# bottom_simp_gyro.net
KiCad netlist of a schematic drawn in Altium Designer
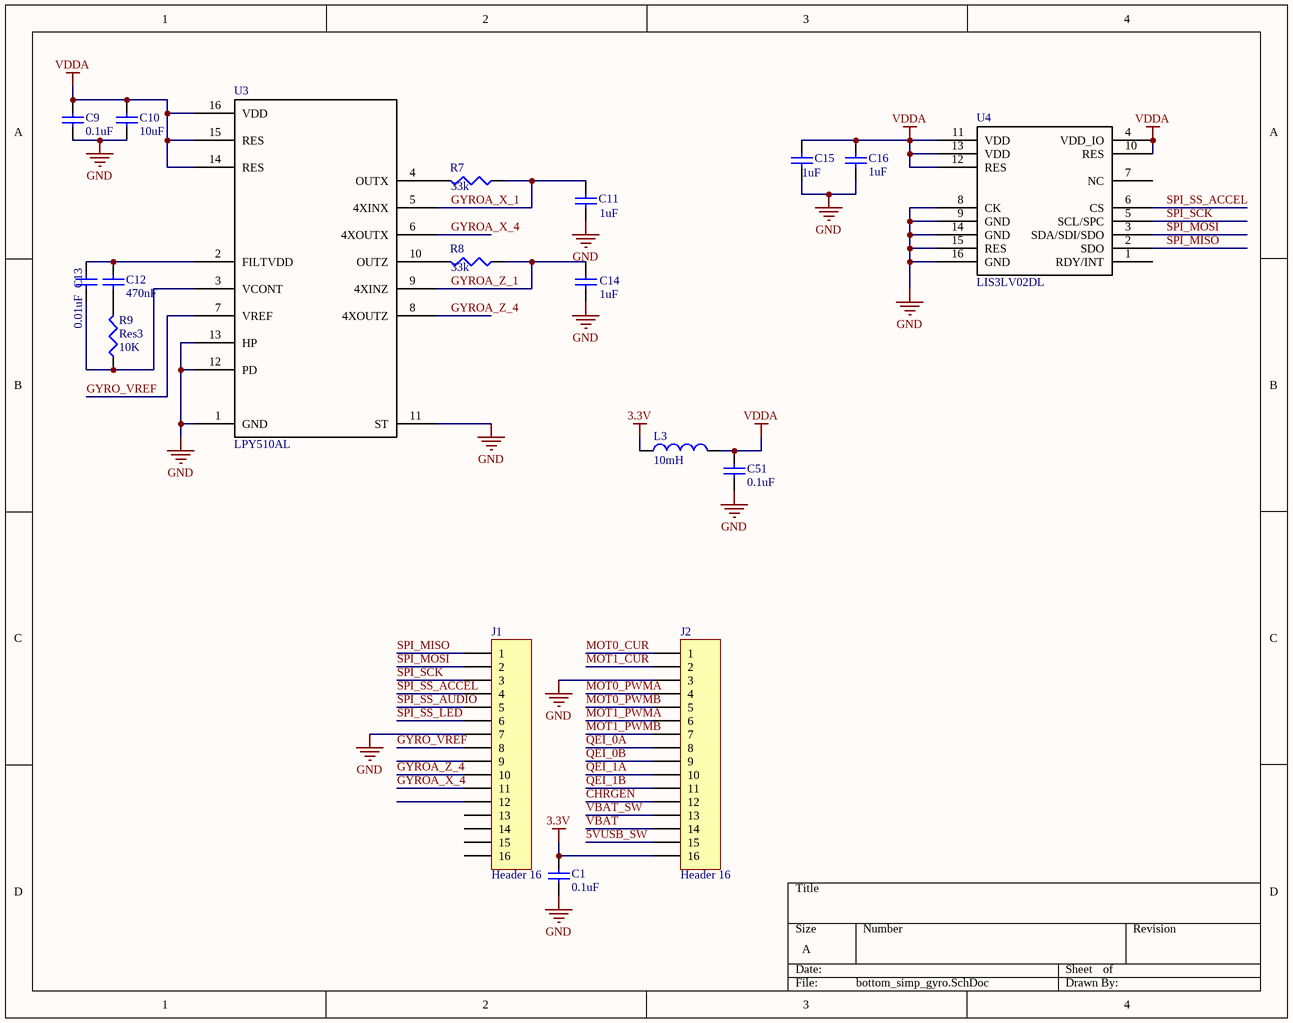
[diagram p0: bottom_simp_gyro.SchDoc]

(export (version "E")
  (design (tool "Eeschema 10.0.6"))
  (components
    (comp (ref "C1")
      (value "0.1uF")
      (footprint "CAPC3216L")
      (description "Capacitor (Semiconductor SIM Model)")
      (fields (field (name "Comment") "Cap Semi") (field (name "PUBLISHER") "Altium Limited"))
      (libsource (lib "Miscellaneous Devices") (part "Cap Semi"))
    )
    (comp (ref "C9")
      (value "0.1uF")
      (footprint "CAPC1005L")
      (description "Capacitor (Semiconductor SIM Model)")
      (fields (field (name "Comment") "Cap Semi") (field (name "PUBLISHER") "Altium Limited"))
      (libsource (lib "Miscellaneous Devices") (part "Cap Semi"))
    )
    (comp (ref "C10")
      (value "10uF")
      (footprint "CAPC1608L")
      (description "Capacitor (Semiconductor SIM Model)")
      (fields (field (name "Comment") "Cap Semi") (field (name "PUBLISHER") "Altium Limited"))
      (libsource (lib "Miscellaneous Devices") (part "Cap Semi"))
    )
    (comp (ref "C11")
      (value "1uF")
      (footprint "CAPC1608L")
      (description "Capacitor (Semiconductor SIM Model)")
      (fields (field (name "Comment") "Cap Semi") (field (name "PUBLISHER") "Altium Limited"))
      (libsource (lib "Miscellaneous Devices") (part "Cap Semi"))
    )
    (comp (ref "C12")
      (value "470nF")
      (footprint "CAPC1005L")
      (description "Capacitor (Semiconductor SIM Model)")
      (fields (field (name "Comment") "Cap Semi") (field (name "PUBLISHER") "Altium Limited"))
      (libsource (lib "Miscellaneous Devices") (part "Cap Semi"))
    )
    (comp (ref "C13")
      (value "0.01uF")
      (footprint "CAPC1005L")
      (description "Capacitor (Semiconductor SIM Model)")
      (fields (field (name "Comment") "Cap Semi") (field (name "PUBLISHER") "Altium Limited"))
      (libsource (lib "Miscellaneous Devices") (part "Cap Semi"))
    )
    (comp (ref "C14")
      (value "1uF")
      (footprint "CAPC1608L")
      (description "Capacitor (Semiconductor SIM Model)")
      (fields (field (name "Comment") "Cap Semi") (field (name "PUBLISHER") "Altium Limited"))
      (libsource (lib "Miscellaneous Devices") (part "Cap Semi"))
    )
    (comp (ref "C15")
      (value "1uF")
      (footprint "CAPC1608L")
      (description "Capacitor (Semiconductor SIM Model)")
      (fields (field (name "Comment") "Cap Semi") (field (name "PUBLISHER") "Altium Limited"))
      (libsource (lib "Miscellaneous Devices") (part "Cap Semi"))
    )
    (comp (ref "C16")
      (value "1uF")
      (footprint "CAPC1608L")
      (description "Capacitor (Semiconductor SIM Model)")
      (fields (field (name "Comment") "Cap Semi") (field (name "PUBLISHER") "Altium Limited"))
      (libsource (lib "Miscellaneous Devices") (part "Cap Semi"))
    )
    (comp (ref "C51")
      (value "0.1uF")
      (footprint "CAPC1005L")
      (description "Capacitor (Semiconductor SIM Model)")
      (fields (field (name "Comment") "Cap Semi") (field (name "PUBLISHER") "Altium Limited"))
      (libsource (lib "Miscellaneous Devices") (part "Cap Semi"))
    )
    (comp (ref "J1")
      (value "Header 16")
      (footprint "HDR1X16")
      (description "Header, 16-Pin")
      (fields (field (name "PUBLISHER") "Altium Limited"))
      (libsource (lib "Miscellaneous Connectors") (part "Header 16"))
    )
    (comp (ref "J2")
      (value "Header 16")
      (footprint "HDR1X16")
      (description "Header, 16-Pin")
      (fields (field (name "PUBLISHER") "Altium Limited"))
      (libsource (lib "Miscellaneous Connectors") (part "Header 16"))
    )
    (comp (ref "L3")
      (value "10mH")
      (footprint "INDC2012L")
      (description "Inductor")
      (fields (field (name "PUBLISHER") "Altium Limited"))
      (libsource (lib "Miscellaneous Devices") (part "Inductor"))
    )
    (comp (ref "R7")
      (value "33k")
      (footprint "RESC1608L")
      (description "Resistor")
      (fields (field (name "Comment") "Res3") (field (name "PUBLISHER") "Altium Limited"))
      (libsource (lib "Miscellaneous Devices") (part "Res3"))
    )
    (comp (ref "R8")
      (value "33k")
      (footprint "RESC1608L")
      (description "Resistor")
      (fields (field (name "Comment") "Res3") (field (name "PUBLISHER") "Altium Limited"))
      (libsource (lib "Miscellaneous Devices") (part "Res3"))
    )
    (comp (ref "R9")
      (value "Res3")
      (footprint "RESC1608L")
      (description "Resistor")
      (fields (field (name "ALTIUM_VALUE") "10K") (field (name "PUBLISHER") "Altium Limited"))
      (libsource (lib "Miscellaneous Devices") (part "Res3"))
    )
    (comp (ref "U3") (value "LPY510AL") (footprint "LGA16") (libsource (lib "mrone") (part "LPY510AL")))
    (comp (ref "U4")
      (value "LIS3LV02DL")
      (footprint "LGA16 (4.4x7.5x1 mm)")
      (libsource (lib "mrone") (part "LIS3LV02DL"))
    )
  )
  (nets
    (net (code "1") (name "/5VUSB_SW") (class "Default")
      (node (ref "J2") (pin "15") (pinfunction "15_15") (pintype "passive"))
    )
    (net (code "2") (name "/CHRGEN") (class "Default")
      (node (ref "J2") (pin "12") (pinfunction "12_12") (pintype "passive"))
    )
    (net (code "3") (name "/GYROA_X_1") (class "Default")
      (node (ref "C11") (pin "2") (pinfunction "2_2") (pintype "passive"))
      (node (ref "R7") (pin "1") (pinfunction "1_1") (pintype "passive"))
      (node (ref "U3") (pin "5") (pinfunction "4XINX_5") (pintype "passive"))
    )
    (net (code "4") (name "/GYROA_X_4") (class "Default")
      (node (ref "J1") (pin "11") (pinfunction "11_11") (pintype "passive"))
      (node (ref "U3") (pin "6") (pinfunction "4XOUTX_6") (pintype "passive"))
    )
    (net (code "5") (name "/GYROA_Z_1") (class "Default")
      (node (ref "C14") (pin "2") (pinfunction "2_2") (pintype "passive"))
      (node (ref "R8") (pin "1") (pinfunction "1_1") (pintype "passive"))
      (node (ref "U3") (pin "9") (pinfunction "4XINZ_9") (pintype "passive"))
    )
    (net (code "6") (name "/GYROA_Z_4") (class "Default")
      (node (ref "J1") (pin "10") (pinfunction "10_10") (pintype "passive"))
      (node (ref "U3") (pin "8") (pinfunction "4XOUTZ_8") (pintype "passive"))
    )
    (net (code "7") (name "/GYRO_VREF") (class "Default")
      (node (ref "J1") (pin "8") (pinfunction "8_8") (pintype "passive"))
      (node (ref "U3") (pin "7") (pinfunction "VREF_7") (pintype "passive"))
    )
    (net (code "8") (name "/MOT0_CUR") (class "Default")
      (node (ref "J2") (pin "1") (pinfunction "1_1") (pintype "passive"))
    )
    (net (code "9") (name "/MOT0_PWMA") (class "Default")
      (node (ref "J2") (pin "4") (pinfunction "4_4") (pintype "passive"))
    )
    (net (code "10") (name "/MOT0_PWMB") (class "Default")
      (node (ref "J2") (pin "5") (pinfunction "5_5") (pintype "passive"))
    )
    (net (code "11") (name "/MOT1_CUR") (class "Default")
      (node (ref "J2") (pin "2") (pinfunction "2_2") (pintype "passive"))
    )
    (net (code "12") (name "/MOT1_PWMA") (class "Default")
      (node (ref "J2") (pin "6") (pinfunction "6_6") (pintype "passive"))
    )
    (net (code "13") (name "/MOT1_PWMB") (class "Default")
      (node (ref "J2") (pin "7") (pinfunction "7_7") (pintype "passive"))
    )
    (net (code "14") (name "/QEI_0A") (class "Default")
      (node (ref "J2") (pin "8") (pinfunction "8_8") (pintype "passive"))
    )
    (net (code "15") (name "/QEI_0B") (class "Default")
      (node (ref "J2") (pin "9") (pinfunction "9_9") (pintype "passive"))
    )
    (net (code "16") (name "/QEI_1A") (class "Default")
      (node (ref "J2") (pin "10") (pinfunction "10_10") (pintype "passive"))
    )
    (net (code "17") (name "/QEI_1B") (class "Default")
      (node (ref "J2") (pin "11") (pinfunction "11_11") (pintype "passive"))
    )
    (net (code "18") (name "/SPI_MISO") (class "Default")
      (node (ref "J1") (pin "1") (pinfunction "1_1") (pintype "passive"))
      (node (ref "U4") (pin "2") (pinfunction "SDO_2") (pintype "passive"))
    )
    (net (code "19") (name "/SPI_MOSI") (class "Default")
      (node (ref "J1") (pin "2") (pinfunction "2_2") (pintype "passive"))
      (node (ref "U4") (pin "3") (pinfunction "SDA/SDI/SDO_3") (pintype "passive"))
    )
    (net (code "20") (name "/SPI_SCK") (class "Default")
      (node (ref "J1") (pin "3") (pinfunction "3_3") (pintype "passive"))
      (node (ref "U4") (pin "5") (pinfunction "SCL/SPC_5") (pintype "passive"))
    )
    (net (code "21") (name "/SPI_SS_ACCEL") (class "Default")
      (node (ref "J1") (pin "4") (pinfunction "4_4") (pintype "passive"))
      (node (ref "U4") (pin "6") (pinfunction "CS_6") (pintype "passive"))
    )
    (net (code "22") (name "/SPI_SS_AUDIO") (class "Default")
      (node (ref "J1") (pin "5") (pinfunction "5_5") (pintype "passive"))
    )
    (net (code "23") (name "/SPI_SS_LED") (class "Default")
      (node (ref "J1") (pin "6") (pinfunction "6_6") (pintype "passive"))
    )
    (net (code "24") (name "/VBAT") (class "Default")
      (node (ref "J2") (pin "14") (pinfunction "14_14") (pintype "passive"))
    )
    (net (code "25") (name "/VBAT_SW") (class "Default")
      (node (ref "J2") (pin "13") (pinfunction "13_13") (pintype "passive"))
    )
    (net (code "26") (name "3.3V") (class "Default")
      (node (ref "C1") (pin "2") (pinfunction "2_2") (pintype "passive"))
      (node (ref "J2") (pin "16") (pinfunction "16_16") (pintype "passive"))
      (node (ref "L3") (pin "2") (pinfunction "2_2") (pintype "passive"))
    )
    (net (code "27") (name "GND") (class "Default")
      (node (ref "C1") (pin "1") (pinfunction "1_1") (pintype "passive"))
      (node (ref "C10") (pin "1") (pinfunction "1_1") (pintype "passive"))
      (node (ref "C11") (pin "1") (pinfunction "1_1") (pintype "passive"))
      (node (ref "C14") (pin "1") (pinfunction "1_1") (pintype "passive"))
      (node (ref "C15") (pin "1") (pinfunction "1_1") (pintype "passive"))
      (node (ref "C16") (pin "1") (pinfunction "1_1") (pintype "passive"))
      (node (ref "C51") (pin "1") (pinfunction "1_1") (pintype "passive"))
      (node (ref "C9") (pin "1") (pinfunction "1_1") (pintype "passive"))
      (node (ref "J1") (pin "7") (pinfunction "7_7") (pintype "passive"))
      (node (ref "J2") (pin "3") (pinfunction "3_3") (pintype "passive"))
      (node (ref "U3") (pin "1") (pinfunction "GND_1") (pintype "passive"))
      (node (ref "U3") (pin "11") (pinfunction "ST_11") (pintype "passive"))
      (node (ref "U3") (pin "12") (pinfunction "PD_12") (pintype "passive"))
      (node (ref "U3") (pin "13") (pinfunction "HP_13") (pintype "passive"))
      (node (ref "U4") (pin "14") (pinfunction "GND_14") (pintype "passive"))
      (node (ref "U4") (pin "15") (pinfunction "RES_15") (pintype "passive"))
      (node (ref "U4") (pin "16") (pinfunction "GND_16") (pintype "passive"))
      (node (ref "U4") (pin "8") (pinfunction "CK_8") (pintype "passive"))
      (node (ref "U4") (pin "9") (pinfunction "GND_9") (pintype "passive"))
    )
    (net (code "28") (name "Net-(C12-Pad1)") (class "Default")
      (node (ref "C12") (pin "1") (pinfunction "1_1") (pintype "passive"))
      (node (ref "R9") (pin "2") (pinfunction "2_2") (pintype "passive"))
    )
    (net (code "29") (name "Net-(U3-FILTVDD)") (class "Default")
      (node (ref "C12") (pin "2") (pinfunction "2_2") (pintype "passive"))
      (node (ref "C13") (pin "2") (pinfunction "2_2") (pintype "passive"))
      (node (ref "U3") (pin "2") (pinfunction "FILTVDD_2") (pintype "passive"))
    )
    (net (code "30") (name "Net-(U3-OUTX)") (class "Default")
      (node (ref "R7") (pin "2") (pinfunction "2_2") (pintype "passive"))
      (node (ref "U3") (pin "4") (pinfunction "OUTX_4") (pintype "passive"))
    )
    (net (code "31") (name "Net-(U3-OUTZ)") (class "Default")
      (node (ref "R8") (pin "2") (pinfunction "2_2") (pintype "passive"))
      (node (ref "U3") (pin "10") (pinfunction "OUTZ_10") (pintype "passive"))
    )
    (net (code "32") (name "Net-(U3-VCONT)") (class "Default")
      (node (ref "C13") (pin "1") (pinfunction "1_1") (pintype "passive"))
      (node (ref "R9") (pin "1") (pinfunction "1_1") (pintype "passive"))
      (node (ref "U3") (pin "3") (pinfunction "VCONT_3") (pintype "passive"))
    )
    (net (code "33") (name "VDDA") (class "Default")
      (node (ref "C10") (pin "2") (pinfunction "2_2") (pintype "passive"))
      (node (ref "C15") (pin "2") (pinfunction "2_2") (pintype "passive"))
      (node (ref "C16") (pin "2") (pinfunction "2_2") (pintype "passive"))
      (node (ref "C51") (pin "2") (pinfunction "2_2") (pintype "passive"))
      (node (ref "C9") (pin "2") (pinfunction "2_2") (pintype "passive"))
      (node (ref "L3") (pin "1") (pinfunction "1_1") (pintype "passive"))
      (node (ref "U3") (pin "14") (pinfunction "RES_14") (pintype "passive"))
      (node (ref "U3") (pin "15") (pinfunction "RES_15") (pintype "passive"))
      (node (ref "U3") (pin "16") (pinfunction "VDD_16") (pintype "passive"))
      (node (ref "U4") (pin "10") (pinfunction "RES_10") (pintype "passive"))
      (node (ref "U4") (pin "11") (pinfunction "VDD_11") (pintype "passive"))
      (node (ref "U4") (pin "12") (pinfunction "RES_12") (pintype "passive"))
      (node (ref "U4") (pin "13") (pinfunction "VDD_13") (pintype "passive"))
      (node (ref "U4") (pin "4") (pinfunction "VDD_IO_4") (pintype "passive"))
    )
    (net (code "34") (name "unconnected-(J1-Pad9)") (class "Default")
      (node (ref "J1") (pin "9") (pinfunction "9_9") (pintype "passive"))
    )
    (net (code "35") (name "unconnected-(J1-Pad12)") (class "Default")
      (node (ref "J1") (pin "12") (pinfunction "12_12") (pintype "passive"))
    )
    (net (code "36") (name "unconnected-(J1-Pad13)") (class "Default")
      (node (ref "J1") (pin "13") (pinfunction "13_13") (pintype "passive"))
    )
    (net (code "37") (name "unconnected-(J1-Pad14)") (class "Default")
      (node (ref "J1") (pin "14") (pinfunction "14_14") (pintype "passive"))
    )
    (net (code "38") (name "unconnected-(J1-Pad15)") (class "Default")
      (node (ref "J1") (pin "15") (pinfunction "15_15") (pintype "passive"))
    )
    (net (code "39") (name "unconnected-(J1-Pad16)") (class "Default")
      (node (ref "J1") (pin "16") (pinfunction "16_16") (pintype "passive"))
    )
    (net (code "40") (name "unconnected-(U4-NC-Pad7)") (class "Default")
      (node (ref "U4") (pin "7") (pinfunction "NC_7") (pintype "passive"))
    )
    (net (code "41") (name "unconnected-(U4-RDY{slash}INT-Pad1)") (class "Default")
      (node (ref "U4") (pin "1") (pinfunction "RDY/INT_1") (pintype "passive"))
    )
  )
)
